# IMU_Breakout_Schematic.net
KiCad netlist of a schematic drawn in Altium Designer
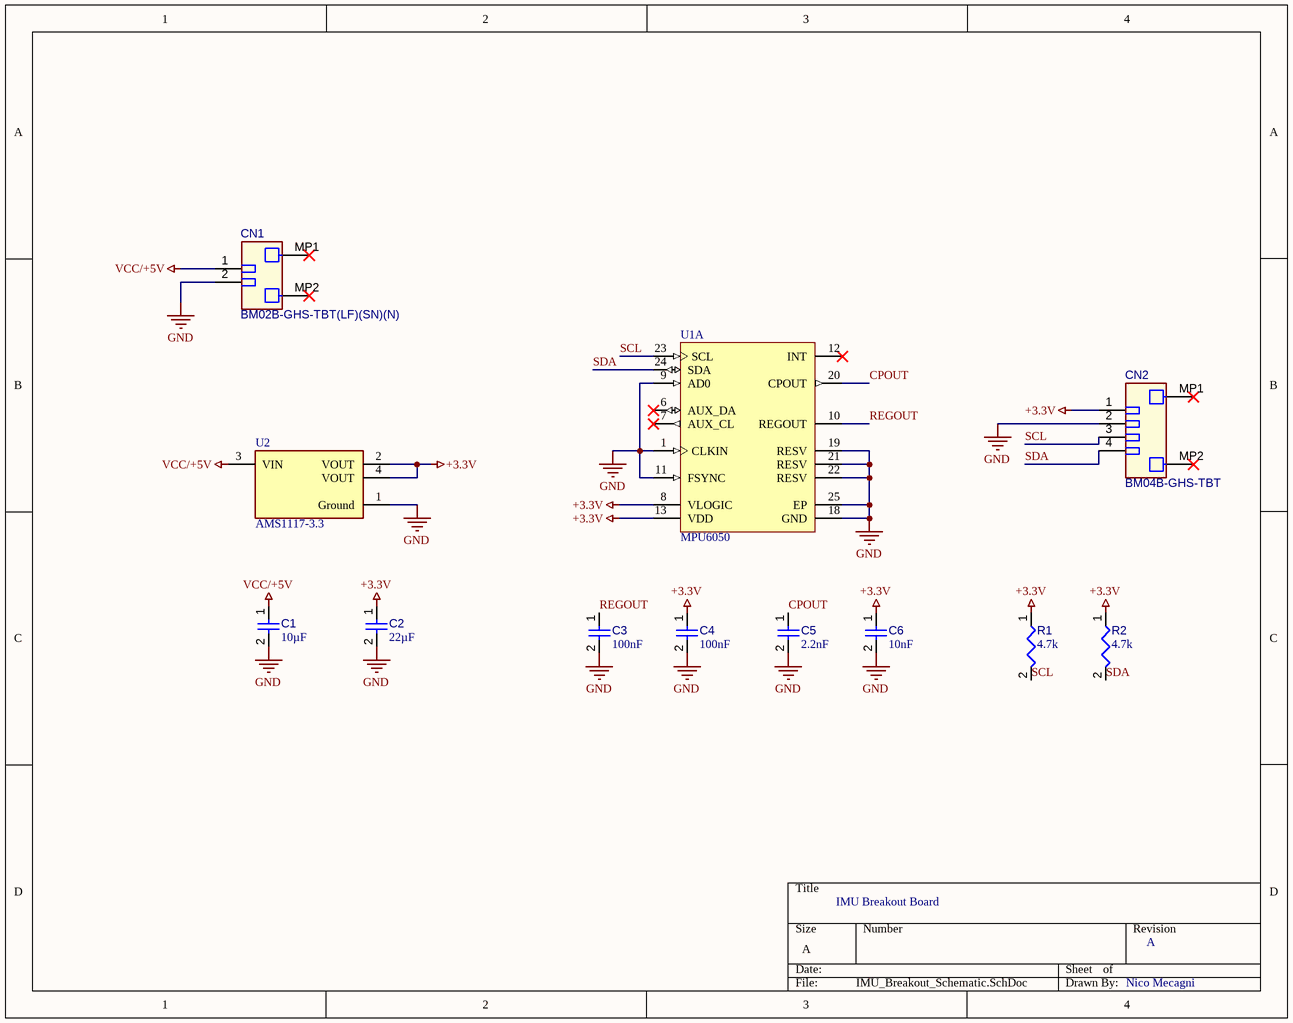
[diagram p0: IMU_Breakout_Schematic.SchDoc]

(export (version "E")
  (design (tool "Eeschema 10.0.6"))
  (components
    (comp (ref "C1")
      (value "10µF")
      (footprint "CAPC0603(1608)100_L")
      (description "Chip Capacitor, 10µF +/-20%, 10V, 0603, Thickness 1 mm")
      (fields (field (name "TOLERANCE") "10%") (field (name "Comment") "Capacitor 10µF +/-20% 10V 0603"))
      (libsource (lib "NMECAGNI") (part "CAP-NP-2"))
    )
    (comp (ref "C2")
      (value "22µF")
      (footprint "CAPC0805(2012)145_L")
      (description "Chip Capacitor, 22µF +/-40%, 16V, 0805, Thickness 1.45 mm")
      (fields (field (name "TOLERANCE") "5%") (field (name "Comment") "Capacitor 22µF +/-40% 16V 0805"))
      (libsource (lib "NMECAGNI") (part "CAP-NP-2"))
    )
    (comp (ref "C3")
      (value "100nF")
      (footprint "CAPC1005X56X25LL10T15")
      (description "Chip Capacitor, 0.1 uF, +/- 5%, 16 V, 0402 (1005 Metric)")
      (fields (field (name "TOLERANCE") "5%") (field (name "Comment") "Capacitor 0.1 uF +/- 5% 16 V 0402"))
      (libsource (lib "NMECAGNI") (part "CAP-NP-2"))
    )
    (comp (ref "C4")
      (value "100nF")
      (footprint "CAPC1005X56X25LL10T15")
      (description "Chip Capacitor, 0.1 uF, +/- 5%, 16 V, 0402 (1005 Metric)")
      (fields (field (name "TOLERANCE") "5%") (field (name "Comment") "Capacitor 0.1 uF +/- 5% 16 V 0402"))
      (libsource (lib "NMECAGNI") (part "CAP-NP-2"))
    )
    (comp (ref "C5")
      (value "2.2nF")
      (footprint "CAPC0402(1005)60_L")
      (description "Chip Capacitor, 2,2µF +/-20%, 10V, 0402, Thickness 0.6 mm")
      (fields (field (name "TOLERANCE") "10%") (field (name "Comment") "Capacitor 2,2µF +/-20% 10V 0402"))
      (libsource (lib "NMECAGNI") (part "CAP-NP-2"))
    )
    (comp (ref "C6")
      (value "10nF")
      (footprint "CAPC0402(1005)60_L")
      (description "Chip Capacitor, 2,2µF +/-20%, 10V, 0402, Thickness 0.6 mm")
      (fields (field (name "TOLERANCE") "10%") (field (name "Comment") "Capacitor 2,2µF +/-20% 10V 0402"))
      (libsource (lib "NMECAGNI") (part "CAP-NP-2"))
    )
    (comp (ref "CN1")
      (value "BM02B-GHS-TBT(LF)(SN)(N)")
      (footprint "JST-BM02B-GHS-TBT_V")
      (libsource (lib "NMECAGNI") (part "CMP-00144-3"))
    )
    (comp (ref "CN2")
      (value "BM04B-GHS-TBT")
      (footprint "JST-BM04B-GHS-TBT_V")
      (description "Header, Pitch 1.25 mm, 1 x 4 Position, Height 4.05 mm, -25 to 85 degC")
      (libsource (lib "NMECAGNI") (part "CMP-00071-3"))
    )
    (comp (ref "R1")
      (value "4.7k")
      (footprint "RESC0805(2012)_L")
      (description "470R 0.125W 5% 0805 (2012 Metric)  SMD")
      (fields (field (name "POWER") "125mW") (field (name "TOLERANCE") "5%"))
      (libsource (lib "NMECAGNI") (part "470R5J"))
    )
    (comp (ref "R2")
      (value "4.7k")
      (footprint "RESC0805(2012)_L")
      (description "470R 0.125W 5% 0805 (2012 Metric)  SMD")
      (fields (field (name "POWER") "125mW") (field (name "TOLERANCE") "5%"))
      (libsource (lib "NMECAGNI") (part "470R5J"))
    )
    (comp (ref "U1")
      (value "MPU6050")
      (footprint "INSE-QFN-24_V")
      (fields (field (name "MANUFACTURER") "InvenSense"))
      (libsource (lib "NMECAGNI") (part "INSE-MPU6050-QFN-24"))
    )
    (comp (ref "U2")
      (value "AMS1117-3.3")
      (footprint "FP-AMS1117-IPC_C")
      (description "LDO Voltage Regulators 1A, 3.3V")
      (fields
        (field (name "OCTOPART") "https://octopart.com/ams1117-3.3-advanced+monolithic+systems-25899300")
        (field (name "MANUFACTURER") "Advanced Monolithic Systems")
      )
      (libsource (lib "Altium Content Vault") (part "8bdbb5f8e77002000e30dd2845d0354"))
    )
  )
  (nets
    (net (code "1") (name "+3.3V") (class "Default")
      (node (ref "C2") (pin "1") (pinfunction "1_1") (pintype "passive"))
      (node (ref "C4") (pin "1") (pinfunction "1_1") (pintype "passive"))
      (node (ref "C6") (pin "1") (pinfunction "1_1") (pintype "passive"))
      (node (ref "CN2") (pin "1") (pinfunction "1_1") (pintype "passive"))
      (node (ref "R1") (pin "1") (pinfunction "1_1") (pintype "passive"))
      (node (ref "R2") (pin "1") (pinfunction "1_1") (pintype "passive"))
      (node (ref "U1") (pin "13") (pinfunction "VDD_13") (pintype "power_in"))
      (node (ref "U1") (pin "8") (pinfunction "VLOGIC_8") (pintype "power_in"))
      (node (ref "U2") (pin "2") (pinfunction "VOUT_2") (pintype "passive"))
      (node (ref "U2") (pin "4") (pinfunction "VOUT_4") (pintype "passive"))
    )
    (net (code "2") (name "/CPOUT") (class "Default")
      (node (ref "C5") (pin "1") (pinfunction "1_1") (pintype "passive"))
      (node (ref "U1") (pin "20") (pinfunction "CPOUT_20") (pintype "output"))
    )
    (net (code "3") (name "/REGOUT") (class "Default")
      (node (ref "C3") (pin "1") (pinfunction "1_1") (pintype "passive"))
      (node (ref "U1") (pin "10") (pinfunction "REGOUT_10") (pintype "passive"))
    )
    (net (code "4") (name "/SCL") (class "Default")
      (node (ref "CN2") (pin "3") (pinfunction "3_3") (pintype "passive"))
      (node (ref "R1") (pin "2") (pinfunction "2_2") (pintype "passive"))
      (node (ref "U1") (pin "23") (pinfunction "SCL_23") (pintype "input"))
    )
    (net (code "5") (name "/SDA") (class "Default")
      (node (ref "CN2") (pin "4") (pinfunction "4_4") (pintype "passive"))
      (node (ref "R2") (pin "2") (pinfunction "2_2") (pintype "passive"))
      (node (ref "U1") (pin "24") (pinfunction "SDA_24") (pintype "bidirectional"))
    )
    (net (code "6") (name "GND") (class "Default")
      (node (ref "C1") (pin "2") (pinfunction "2_2") (pintype "passive"))
      (node (ref "C2") (pin "2") (pinfunction "2_2") (pintype "passive"))
      (node (ref "C3") (pin "2") (pinfunction "2_2") (pintype "passive"))
      (node (ref "C4") (pin "2") (pinfunction "2_2") (pintype "passive"))
      (node (ref "C5") (pin "2") (pinfunction "2_2") (pintype "passive"))
      (node (ref "C6") (pin "2") (pinfunction "2_2") (pintype "passive"))
      (node (ref "CN1") (pin "2") (pinfunction "2_2") (pintype "passive"))
      (node (ref "CN2") (pin "2") (pinfunction "2_2") (pintype "passive"))
      (node (ref "U1") (pin "1") (pinfunction "CLKIN_1") (pintype "input"))
      (node (ref "U1") (pin "11") (pinfunction "FSYNC_11") (pintype "input"))
      (node (ref "U1") (pin "18") (pinfunction "GND_18") (pintype "power_in"))
      (node (ref "U1") (pin "19") (pinfunction "RESV_19") (pintype "passive"))
      (node (ref "U1") (pin "21") (pinfunction "RESV_21") (pintype "passive"))
      (node (ref "U1") (pin "22") (pinfunction "RESV_22") (pintype "passive"))
      (node (ref "U1") (pin "25") (pinfunction "EP_25") (pintype "passive"))
      (node (ref "U1") (pin "9") (pinfunction "AD0_9") (pintype "input"))
      (node (ref "U2") (pin "1") (pinfunction "Ground_1") (pintype "power_in"))
    )
    (net (code "7") (name "VCC{slash}+5V") (class "Default")
      (node (ref "C1") (pin "1") (pinfunction "1_1") (pintype "passive"))
      (node (ref "CN1") (pin "1") (pinfunction "1_1") (pintype "passive"))
      (node (ref "U2") (pin "3") (pinfunction "VIN_3") (pintype "power_in"))
    )
    (net (code "8") (name "unconnected-(CN1-PadMP1)") (class "Default")
      (node (ref "CN1") (pin "MP1") (pinfunction "MP1_MP1") (pintype "passive+no_connect"))
    )
    (net (code "9") (name "unconnected-(CN1-PadMP2)") (class "Default")
      (node (ref "CN1") (pin "MP2") (pinfunction "MP2_MP2") (pintype "passive+no_connect"))
    )
    (net (code "10") (name "unconnected-(CN2-PadMP1)") (class "Default")
      (node (ref "CN2") (pin "MP1") (pinfunction "MP1_MP1") (pintype "passive+no_connect"))
    )
    (net (code "11") (name "unconnected-(CN2-PadMP2)") (class "Default")
      (node (ref "CN2") (pin "MP2") (pinfunction "MP2_MP2") (pintype "passive+no_connect"))
    )
    (net (code "12") (name "unconnected-(U1A-AUX_CL-Pad7)") (class "Default")
      (node (ref "U1") (pin "7") (pinfunction "AUX_CL_7") (pintype "output+no_connect"))
    )
    (net (code "13") (name "unconnected-(U1A-AUX_DA-Pad6)") (class "Default")
      (node (ref "U1") (pin "6") (pinfunction "AUX_DA_6") (pintype "bidirectional+no_connect"))
    )
    (net (code "14") (name "unconnected-(U1A-INT-Pad12)") (class "Default")
      (node (ref "U1") (pin "12") (pinfunction "INT_12") (pintype "open_collector+no_connect"))
    )
  )
)
